# 04_Storage_Sensor.net
KiCad netlist of a schematic drawn in Altium Designer
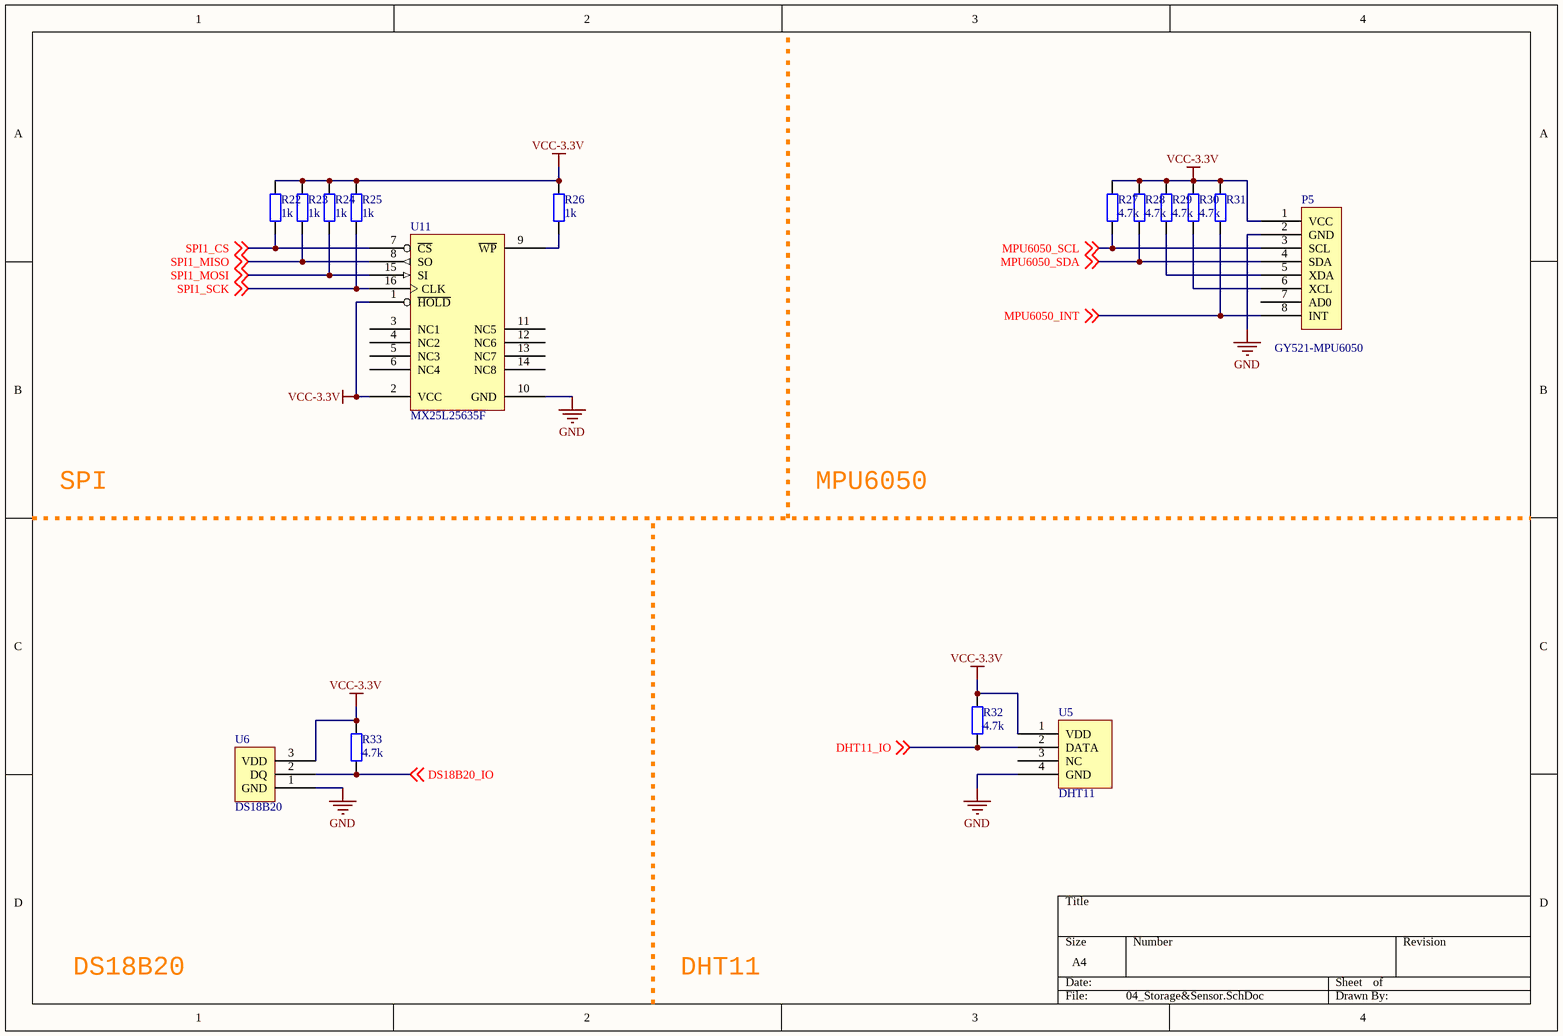
[diagram p0: 04_Storage&Sensor.SchDoc]

(export (version "E")
  (design (tool "Eeschema 10.0.6"))
  (components
    (comp (ref "P5")
      (value "GY521-MPU6050")
      (footprint "GY521-MPU6050")
      (fields (field (name "MANUFACTURER") "Invensense") (field (name "MANUFACTURER PART NUMBER") "MPU-6050"))
      (libsource (lib "Miscellaneous Modules") (part "GY521-MPU6050"))
    )
    (comp (ref "R22")
      (value "1k")
      (footprint "AXIAL-0.3")
      (description "贴片电阻")
      (fields (field (name "Comment") "10k") (field (name "PUBLISHER") "Altium Limited"))
      (libsource (lib "") (part "Res1_1"))
    )
    (comp (ref "R23")
      (value "1k")
      (footprint "AXIAL-0.3")
      (description "贴片电阻")
      (fields (field (name "Comment") "10k") (field (name "PUBLISHER") "Altium Limited"))
      (libsource (lib "fszhang") (part "Res1"))
    )
    (comp (ref "R24")
      (value "1k")
      (footprint "AXIAL-0.3")
      (description "贴片电阻")
      (fields (field (name "Comment") "10k") (field (name "PUBLISHER") "Altium Limited"))
      (libsource (lib "fszhang") (part "Res1"))
    )
    (comp (ref "R25")
      (value "1k")
      (footprint "AXIAL-0.3")
      (description "贴片电阻")
      (fields (field (name "Comment") "10k") (field (name "PUBLISHER") "Altium Limited"))
      (libsource (lib "fszhang") (part "Res1"))
    )
    (comp (ref "R26")
      (value "1k")
      (footprint "AXIAL-0.3")
      (description "贴片电阻")
      (fields (field (name "Comment") "10k") (field (name "PUBLISHER") "Altium Limited"))
      (libsource (lib "fszhang") (part "Res1"))
    )
    (comp (ref "R27")
      (value "4.7k")
      (footprint "AXIAL-0.3")
      (description "贴片电阻")
      (fields (field (name "Comment") "10k") (field (name "PUBLISHER") "Altium Limited"))
      (libsource (lib "") (part "Res1_1"))
    )
    (comp (ref "R28")
      (value "4.7k")
      (footprint "AXIAL-0.3")
      (description "贴片电阻")
      (fields (field (name "Comment") "10k") (field (name "PUBLISHER") "Altium Limited"))
      (libsource (lib "") (part "Res1_1"))
    )
    (comp (ref "R29")
      (value "4.7k")
      (footprint "AXIAL-0.3")
      (description "贴片电阻")
      (fields (field (name "Comment") "10k") (field (name "PUBLISHER") "Altium Limited"))
      (libsource (lib "") (part "Res1_1"))
    )
    (comp (ref "R30")
      (value "4.7k")
      (footprint "AXIAL-0.3")
      (description "贴片电阻")
      (fields (field (name "Comment") "10k") (field (name "PUBLISHER") "Altium Limited"))
      (libsource (lib "") (part "Res1_1"))
    )
    (comp (ref "R31")
      (value "10k")
      (footprint "AXIAL-0.3")
      (description "贴片电阻")
      (fields (field (name "PUBLISHER") "Altium Limited"))
      (libsource (lib "") (part "Res1_1"))
    )
    (comp (ref "R32")
      (value "4.7k")
      (footprint "AXIAL-0.3")
      (description "贴片电阻")
      (fields (field (name "Comment") "10k") (field (name "PUBLISHER") "Altium Limited"))
      (libsource (lib "") (part "Res1_1"))
    )
    (comp (ref "R33")
      (value "4.7k")
      (footprint "Miscellaneous Modules:AXIAL-0.3")
      (description "贴片电阻")
      (fields (field (name "Comment") "10k") (field (name "PUBLISHER") "Altium Limited"))
      (libsource (lib "") (part "Res1_1"))
    )
    (comp (ref "U5")
      (value "DHT11")
      (footprint "DHT-11")
      (fields (field (name "MANUFACTURER") "Sensirion") (field (name "MANUFACTURER PART NUMBER") "SHT11"))
      (libsource (lib "Miscellaneous Modules") (part "DHT11"))
    )
    (comp (ref "U6")
      (value "DS18B20")
      (footprint "TO-92")
      (fields (field (name "MANUFACTURER") "Maxim") (field (name "MANUFACTURER PART NUMBER") "DS18B20+"))
      (libsource (lib "Miscellaneous Modules") (part "DS18B20"))
    )
    (comp (ref "U11")
      (value "MX25L25635F")
      (footprint "SOL-16_M")
      (description "IC FLASH 256MBIT 104MHZ 16SOP")
      (fields
        (field (name "MANUFACTURER") "Macronix")
        (field (name "MANUFACTURER PART NUMBER") "MX25L25635FMI-10G")
      )
      (libsource (lib "Miscellaneous Modules") (part "MX25L25635F"))
    )
  )
  (nets
    (net (code "1") (name "DHT11_IO") (class "Default")
      (node (ref "R32") (pin "2") (pinfunction "2_2") (pintype "passive"))
      (node (ref "U5") (pin "2") (pinfunction "DATA_2") (pintype "passive"))
    )
    (net (code "2") (name "DS18B20_IO") (class "Default")
      (node (ref "R33") (pin "2") (pinfunction "2_2") (pintype "passive"))
      (node (ref "U6") (pin "2") (pinfunction "DQ_2") (pintype "passive"))
    )
    (net (code "3") (name "GND") (class "Default")
      (node (ref "P5") (pin "2") (pinfunction "GND_2") (pintype "passive"))
      (node (ref "U11") (pin "10") (pinfunction "GND_10") (pintype "passive"))
      (node (ref "U5") (pin "4") (pinfunction "GND_4") (pintype "passive"))
      (node (ref "U6") (pin "1") (pinfunction "GND_1") (pintype "passive"))
    )
    (net (code "4") (name "MPU6050_INT") (class "Default")
      (node (ref "P5") (pin "8") (pinfunction "INT_8") (pintype "passive"))
      (node (ref "R31") (pin "2") (pinfunction "2_2") (pintype "passive"))
    )
    (net (code "5") (name "MPU6050_SCL") (class "Default")
      (node (ref "P5") (pin "3") (pinfunction "SCL_3") (pintype "passive"))
      (node (ref "R27") (pin "2") (pinfunction "2_2") (pintype "passive"))
    )
    (net (code "6") (name "MPU6050_SDA") (class "Default")
      (node (ref "P5") (pin "4") (pinfunction "SDA_4") (pintype "passive"))
      (node (ref "R28") (pin "2") (pinfunction "2_2") (pintype "passive"))
    )
    (net (code "7") (name "Net-(P5-XCL)") (class "Default")
      (node (ref "P5") (pin "6") (pinfunction "XCL_6") (pintype "passive"))
      (node (ref "R30") (pin "2") (pinfunction "2_2") (pintype "passive"))
    )
    (net (code "8") (name "Net-(P5-XDA)") (class "Default")
      (node (ref "P5") (pin "5") (pinfunction "XDA_5") (pintype "passive"))
      (node (ref "R29") (pin "2") (pinfunction "2_2") (pintype "passive"))
    )
    (net (code "9") (name "Net-(U11-~{WP})") (class "Default")
      (node (ref "R26") (pin "1") (pinfunction "1_1") (pintype "passive"))
      (node (ref "U11") (pin "9") (pinfunction "~{WP}_9") (pintype "passive"))
    )
    (net (code "10") (name "SPI1_CS") (class "Default")
      (node (ref "R22") (pin "2") (pinfunction "2_2") (pintype "passive"))
      (node (ref "U11") (pin "7") (pinfunction "~{CS}_7") (pintype "passive"))
    )
    (net (code "11") (name "SPI1_MISO") (class "Default")
      (node (ref "R23") (pin "1") (pinfunction "1_1") (pintype "passive"))
      (node (ref "U11") (pin "8") (pinfunction "SO_8") (pintype "output"))
    )
    (net (code "12") (name "SPI1_MOSI") (class "Default")
      (node (ref "R24") (pin "1") (pinfunction "1_1") (pintype "passive"))
      (node (ref "U11") (pin "15") (pinfunction "SI_15") (pintype "input"))
    )
    (net (code "13") (name "SPI1_SCK") (class "Default")
      (node (ref "R25") (pin "1") (pinfunction "1_1") (pintype "passive"))
      (node (ref "U11") (pin "16") (pinfunction "CLK_16") (pintype "passive"))
    )
    (net (code "14") (name "VCC-3.3V") (class "Default")
      (node (ref "P5") (pin "1") (pinfunction "VCC_1") (pintype "passive"))
      (node (ref "R22") (pin "1") (pinfunction "1_1") (pintype "passive"))
      (node (ref "R23") (pin "2") (pinfunction "2_2") (pintype "passive"))
      (node (ref "R24") (pin "2") (pinfunction "2_2") (pintype "passive"))
      (node (ref "R25") (pin "2") (pinfunction "2_2") (pintype "passive"))
      (node (ref "R26") (pin "2") (pinfunction "2_2") (pintype "passive"))
      (node (ref "R27") (pin "1") (pinfunction "1_1") (pintype "passive"))
      (node (ref "R28") (pin "1") (pinfunction "1_1") (pintype "passive"))
      (node (ref "R29") (pin "1") (pinfunction "1_1") (pintype "passive"))
      (node (ref "R30") (pin "1") (pinfunction "1_1") (pintype "passive"))
      (node (ref "R31") (pin "1") (pinfunction "1_1") (pintype "passive"))
      (node (ref "R32") (pin "1") (pinfunction "1_1") (pintype "passive"))
      (node (ref "R33") (pin "1") (pinfunction "1_1") (pintype "passive"))
      (node (ref "U11") (pin "1") (pinfunction "~{HOLD}_1") (pintype "passive"))
      (node (ref "U11") (pin "2") (pinfunction "VCC_2") (pintype "passive"))
      (node (ref "U5") (pin "1") (pinfunction "VDD_1") (pintype "passive"))
      (node (ref "U6") (pin "3") (pinfunction "VDD_3") (pintype "passive"))
    )
    (net (code "15") (name "unconnected-(P5-AD0-Pad7)") (class "Default")
      (node (ref "P5") (pin "7") (pinfunction "AD0_7") (pintype "passive"))
    )
    (net (code "16") (name "unconnected-(U5-NC-Pad3)") (class "Default")
      (node (ref "U5") (pin "3") (pinfunction "NC_3") (pintype "passive"))
    )
    (net (code "17") (name "unconnected-(U11-NC1-Pad3)") (class "Default")
      (node (ref "U11") (pin "3") (pinfunction "NC1_3") (pintype "passive"))
    )
    (net (code "18") (name "unconnected-(U11-NC2-Pad4)") (class "Default")
      (node (ref "U11") (pin "4") (pinfunction "NC2_4") (pintype "passive"))
    )
    (net (code "19") (name "unconnected-(U11-NC3-Pad5)") (class "Default")
      (node (ref "U11") (pin "5") (pinfunction "NC3_5") (pintype "passive"))
    )
    (net (code "20") (name "unconnected-(U11-NC4-Pad6)") (class "Default")
      (node (ref "U11") (pin "6") (pinfunction "NC4_6") (pintype "passive"))
    )
    (net (code "21") (name "unconnected-(U11-NC5-Pad11)") (class "Default")
      (node (ref "U11") (pin "11") (pinfunction "NC5_11") (pintype "passive"))
    )
    (net (code "22") (name "unconnected-(U11-NC6-Pad12)") (class "Default")
      (node (ref "U11") (pin "12") (pinfunction "NC6_12") (pintype "passive"))
    )
    (net (code "23") (name "unconnected-(U11-NC7-Pad13)") (class "Default")
      (node (ref "U11") (pin "13") (pinfunction "NC7_13") (pintype "passive"))
    )
    (net (code "24") (name "unconnected-(U11-NC8-Pad14)") (class "Default")
      (node (ref "U11") (pin "14") (pinfunction "NC8_14") (pintype "passive"))
    )
  )
)
